# 2led_Arduino_V2.net
KiCad netlist of a schematic drawn in EAGLE
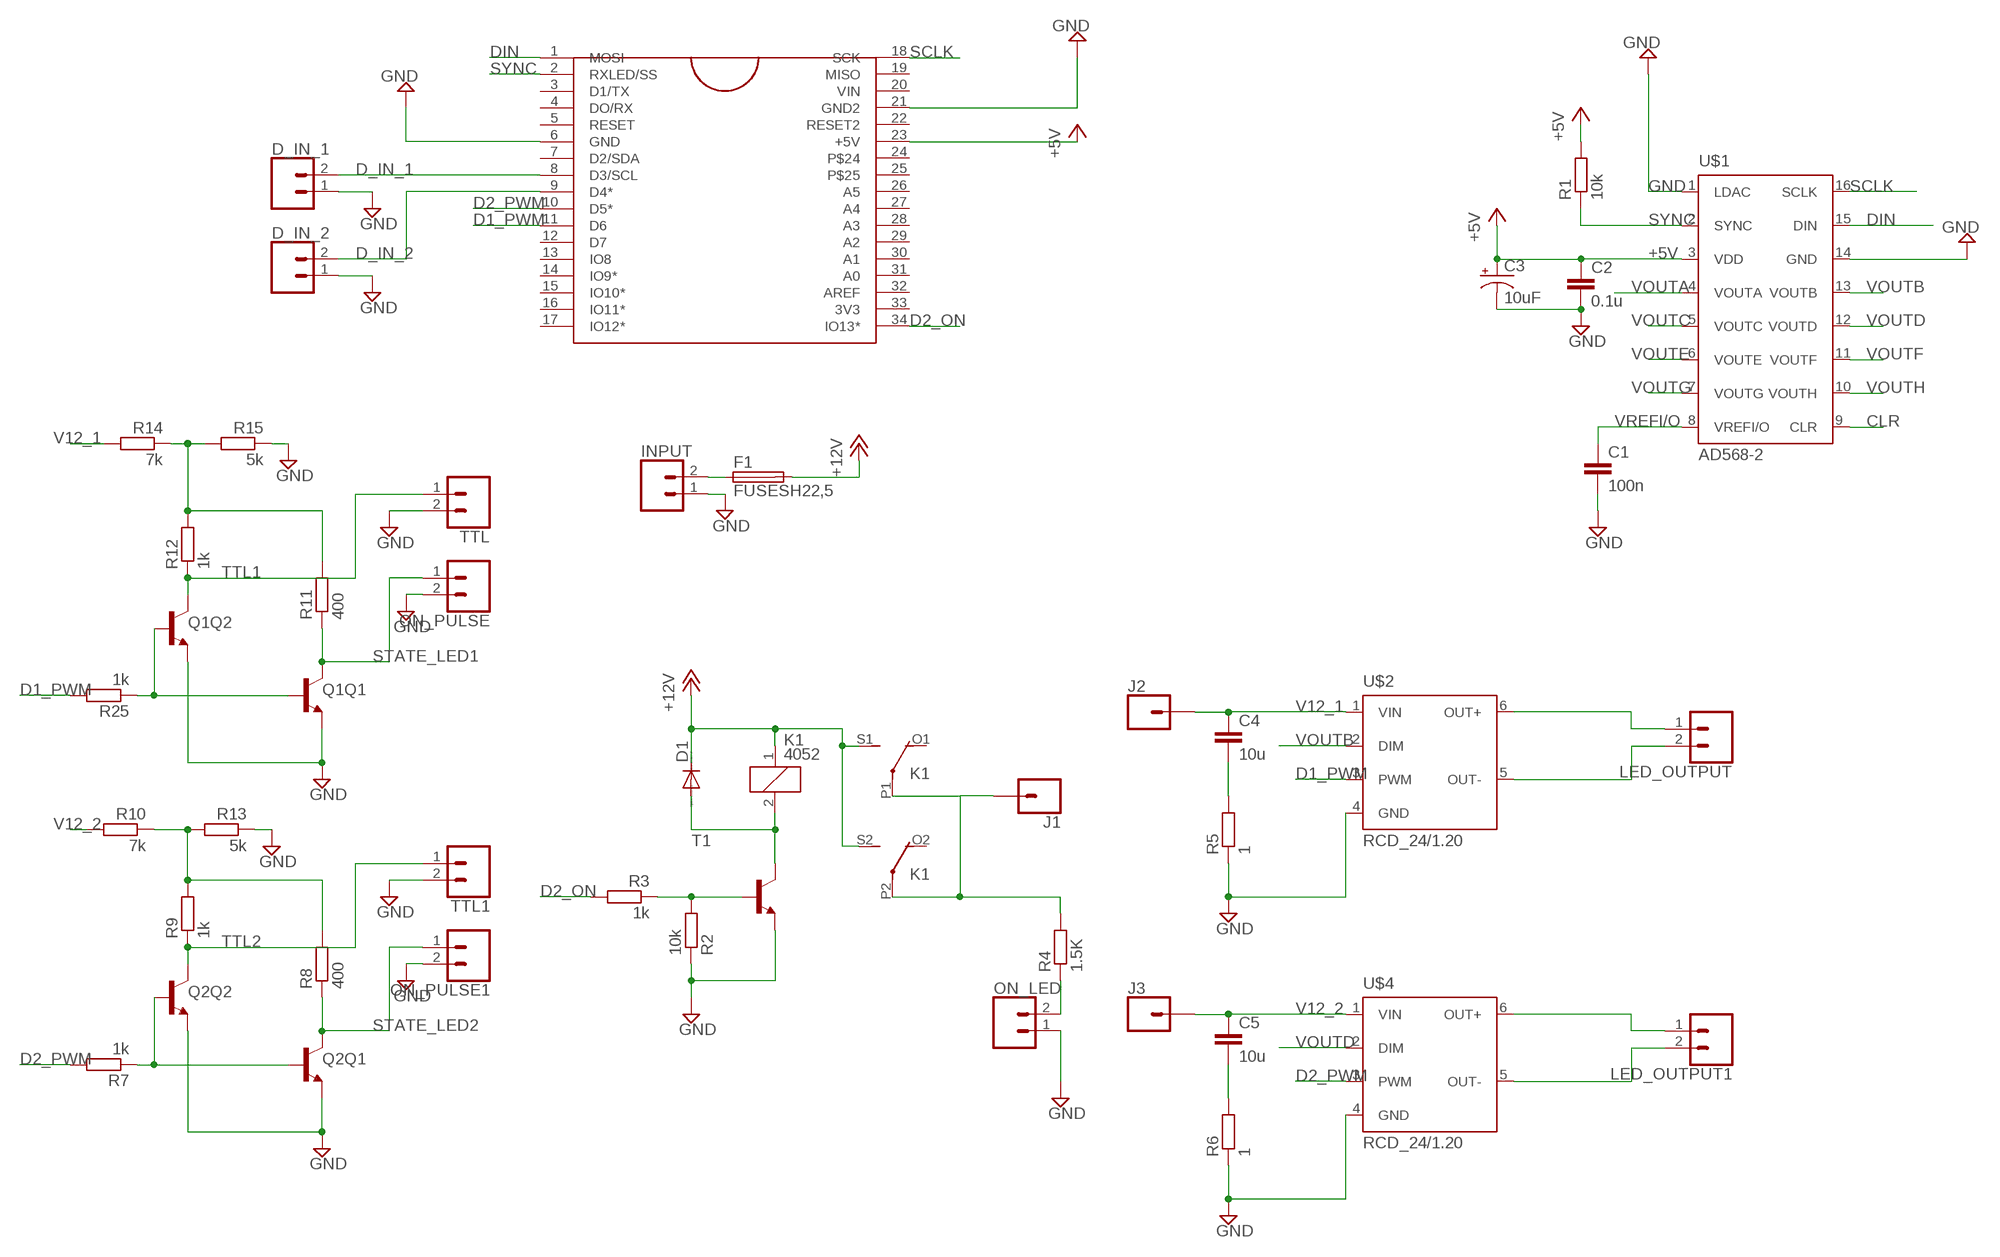
[diagram p0: schematic, sheet 1]

(export (version "E")
  (design (tool "Eeschema 10.0.6"))
  (components
    (comp (ref "C1")
      (value "100n")
      (footprint "eagle-import:C1206")
      (libsource (lib "eagle-import") (part "C-EUC1206"))
    )
    (comp (ref "C2")
      (value "0.1u")
      (footprint "eagle-import:C1206")
      (libsource (lib "eagle-import") (part "C-EUC1206"))
    )
    (comp (ref "C3")
      (value "10uF")
      (footprint "eagle-import:EIA3528")
      (libsource (lib "eagle-import") (part "10UF-POLAR-EIA3528-20V-10%(TANT)"))
    )
    (comp (ref "C4")
      (value "10u")
      (footprint "eagle-import:C1206")
      (libsource (lib "eagle-import") (part "C-EUC1206"))
    )
    (comp (ref "C5")
      (value "10u")
      (footprint "eagle-import:C1206")
      (libsource (lib "eagle-import") (part "C-EUC1206"))
    )
    (comp (ref "D1")
      (value "DIODE-DO214AC")
      (footprint "eagle-import:DO214AC")
      (libsource (lib "eagle-import") (part "DIODE-DO214AC"))
    )
    (comp (ref "D_IN_1")
      (value "CONN_02")
      (footprint "eagle-import:1X02")
      (libsource (lib "eagle-import") (part "CONN_02"))
    )
    (comp (ref "D_IN_2")
      (value "CONN_02")
      (footprint "eagle-import:1X02")
      (libsource (lib "eagle-import") (part "CONN_02"))
    )
    (comp (ref "F1")
      (value "FUSESH22,5")
      (footprint "eagle-import:SH22,5")
      (libsource (lib "eagle-import") (part "FUSESH22,5"))
    )
    (comp (ref "INPUT")
      (value "CONN_023.5MM")
      (footprint "eagle-import:SCREWTERMINAL-3.5MM-2")
      (libsource (lib "eagle-import") (part "CONN_023.5MM"))
    )
    (comp (ref "J1")
      (value "CONN_01")
      (footprint "eagle-import:1X01")
      (libsource (lib "eagle-import") (part "CONN_01"))
    )
    (comp (ref "J2")
      (value "CONN_01")
      (footprint "eagle-import:1X01")
      (libsource (lib "eagle-import") (part "CONN_01"))
    )
    (comp (ref "J3")
      (value "CONN_01")
      (footprint "eagle-import:1X01")
      (libsource (lib "eagle-import") (part "CONN_01"))
    )
    (comp (ref "K1")
      (value "4052")
      (footprint "eagle-import:F4052")
      (libsource (lib "eagle-import") (part "4052"))
    )
    (comp (ref "LED_OUTPUT")
      (value "CONN_023.5MM")
      (footprint "eagle-import:SCREWTERMINAL-3.5MM-2")
      (libsource (lib "eagle-import") (part "CONN_023.5MM"))
    )
    (comp (ref "LED_OUTPUT1")
      (value "CONN_023.5MM")
      (footprint "eagle-import:SCREWTERMINAL-3.5MM-2")
      (libsource (lib "eagle-import") (part "CONN_023.5MM"))
    )
    (comp (ref "ON_LED")
      (value "CONN_02")
      (footprint "eagle-import:1X02")
      (libsource (lib "eagle-import") (part "CONN_02"))
    )
    (comp (ref "ON_PULSE")
      (value "CONN_02")
      (footprint "eagle-import:1X02")
      (libsource (lib "eagle-import") (part "CONN_02"))
    )
    (comp (ref "ON_PULSE1")
      (value "CONN_02")
      (footprint "eagle-import:1X02")
      (libsource (lib "eagle-import") (part "CONN_02"))
    )
    (comp (ref "Q1")
      (value "TRANS_NPN_DUAL_NSM4002-MBT3904DW1T1")
      (footprint "eagle-import:SC70-6")
      (libsource (lib "eagle-import") (part "TRANS_NPN_DUAL_NSM4002-MBT3904DW1T1"))
    )
    (comp (ref "Q2")
      (value "TRANS_NPN_DUAL_NSM4002-MBT3904DW1T1")
      (footprint "eagle-import:SC70-6")
      (libsource (lib "eagle-import") (part "TRANS_NPN_DUAL_NSM4002-MBT3904DW1T1"))
    )
    (comp (ref "R1")
      (value "10k")
      (footprint "eagle-import:R0805")
      (libsource (lib "eagle-import") (part "R-EU_R0805"))
    )
    (comp (ref "R2")
      (value "10k")
      (footprint "eagle-import:R0805")
      (libsource (lib "eagle-import") (part "R-EU_R0805"))
    )
    (comp (ref "R3")
      (value "1k")
      (footprint "eagle-import:R0805")
      (libsource (lib "eagle-import") (part "R-EU_R0805"))
    )
    (comp (ref "R4")
      (value "1.5K")
      (footprint "eagle-import:R0805")
      (libsource (lib "eagle-import") (part "R-EU_R0805"))
    )
    (comp (ref "R5")
      (value "1")
      (footprint "eagle-import:R1206")
      (libsource (lib "eagle-import") (part "R-EU_R1206"))
    )
    (comp (ref "R6")
      (value "1")
      (footprint "eagle-import:R1206")
      (libsource (lib "eagle-import") (part "R-EU_R1206"))
    )
    (comp (ref "R7")
      (value "1k")
      (footprint "eagle-import:R0805")
      (libsource (lib "eagle-import") (part "R-EU_R0805"))
    )
    (comp (ref "R8")
      (value "400")
      (footprint "eagle-import:R0805")
      (libsource (lib "eagle-import") (part "R-EU_R0805"))
    )
    (comp (ref "R9")
      (value "1k")
      (footprint "eagle-import:R0805")
      (libsource (lib "eagle-import") (part "R-EU_R0805"))
    )
    (comp (ref "R10")
      (value "7k")
      (footprint "eagle-import:R0805")
      (libsource (lib "eagle-import") (part "R-EU_R0805"))
    )
    (comp (ref "R11")
      (value "400")
      (footprint "eagle-import:R0805")
      (libsource (lib "eagle-import") (part "R-EU_R0805"))
    )
    (comp (ref "R12")
      (value "1k")
      (footprint "eagle-import:R0805")
      (libsource (lib "eagle-import") (part "R-EU_R0805"))
    )
    (comp (ref "R13")
      (value "5k")
      (footprint "eagle-import:R0805")
      (libsource (lib "eagle-import") (part "R-EU_R0805"))
    )
    (comp (ref "R14")
      (value "7k")
      (footprint "eagle-import:R0805")
      (libsource (lib "eagle-import") (part "R-EU_R0805"))
    )
    (comp (ref "R15")
      (value "5k")
      (footprint "eagle-import:R0805")
      (libsource (lib "eagle-import") (part "R-EU_R0805"))
    )
    (comp (ref "R25")
      (value "1k")
      (footprint "eagle-import:R0805")
      (libsource (lib "eagle-import") (part "R-EU_R0805"))
    )
    (comp (ref "T1")
      (value "-NPN-SOT223")
      (footprint "eagle-import:SOT223")
      (libsource (lib "eagle-import") (part "-NPN-SOT223"))
    )
    (comp (ref "TTL")
      (value "CONN_02")
      (footprint "eagle-import:1X02")
      (libsource (lib "eagle-import") (part "CONN_02"))
    )
    (comp (ref "TTL1")
      (value "CONN_02")
      (footprint "eagle-import:1X02")
      (libsource (lib "eagle-import") (part "CONN_02"))
    )
    (comp (ref "U$1")
      (value "AD568-2")
      (footprint "eagle-import:TSSOP-16")
      (libsource (lib "eagle-import") (part "AD568-2"))
    )
    (comp (ref "U$2")
      (value "RCD_24/1.20")
      (footprint "eagle-import:RCD-24_W_X3")
      (libsource (lib "eagle-import") (part "RCD_24/1.20"))
    )
    (comp (ref "U$3")
      (value "ARDUINO_MICRO")
      (footprint "eagle-import:ARDUINO_MICRO_PADS")
      (fields (field (name "SPICEPREFIX") "X"))
      (libsource (lib "eagle-import") (part "ARDUINO_MICRO"))
    )
    (comp (ref "U$4")
      (value "RCD_24/1.20")
      (footprint "eagle-import:RCD-24_W_X3")
      (libsource (lib "eagle-import") (part "RCD_24/1.20"))
    )
  )
  (nets
    (net (code "1") (name "+5V") (class "Default")
      (node (ref "C2") (pin "1") (pinfunction "1_1") (pintype "passive"))
      (node (ref "C3") (pin "A") (pinfunction "+_A") (pintype "passive"))
      (node (ref "R1") (pin "2") (pinfunction "2_2") (pintype "passive"))
      (node (ref "U$1") (pin "3") (pinfunction "VDD_3") (pintype "power_in"))
      (node (ref "U$3") (pin "23") (pinfunction "+5V_23") (pintype "bidirectional"))
    )
    (net (code "2") (name "+12V") (class "Default")
      (node (ref "D1") (pin "C") (pinfunction "C_C") (pintype "passive"))
      (node (ref "F1") (pin "2") (pinfunction "2_2") (pintype "passive"))
      (node (ref "K1") (pin "1") (pinfunction "1_1") (pintype "passive"))
      (node (ref "K1") (pin "S1") (pinfunction "S_S1") (pintype "passive"))
      (node (ref "K1") (pin "S2") (pinfunction "S_S2") (pintype "passive"))
    )
    (net (code "3") (name "/CLR") (class "Default")
      (node (ref "U$1") (pin "9") (pinfunction "CLR_9") (pintype "output"))
    )
    (net (code "4") (name "/D1_PWM") (class "Default")
      (node (ref "R25") (pin "2") (pinfunction "2_2") (pintype "passive"))
      (node (ref "U$2") (pin "3") (pinfunction "PWM_3") (pintype "passive"))
      (node (ref "U$3") (pin "11") (pinfunction "D6_11") (pintype "bidirectional"))
    )
    (net (code "5") (name "/D2_ON") (class "Default")
      (node (ref "R3") (pin "2") (pinfunction "2_2") (pintype "passive"))
      (node (ref "U$3") (pin "34") (pinfunction "IO13*_34") (pintype "bidirectional"))
    )
    (net (code "6") (name "/D2_PWM") (class "Default")
      (node (ref "R7") (pin "2") (pinfunction "2_2") (pintype "passive"))
      (node (ref "U$3") (pin "10") (pinfunction "D5*_10") (pintype "bidirectional"))
      (node (ref "U$4") (pin "3") (pinfunction "PWM_3") (pintype "passive"))
    )
    (net (code "7") (name "/DIN") (class "Default")
      (node (ref "U$1") (pin "15") (pinfunction "DIN_15") (pintype "input"))
      (node (ref "U$3") (pin "1") (pinfunction "MOSI_1") (pintype "bidirectional"))
    )
    (net (code "8") (name "/D_IN_1") (class "Default")
      (node (ref "D_IN_1") (pin "2") (pinfunction "2_2") (pintype "passive"))
      (node (ref "U$3") (pin "8") (pinfunction "D3/SCL_8") (pintype "bidirectional"))
    )
    (net (code "9") (name "/D_IN_2") (class "Default")
      (node (ref "D_IN_2") (pin "2") (pinfunction "2_2") (pintype "passive"))
      (node (ref "U$3") (pin "9") (pinfunction "D4*_9") (pintype "bidirectional"))
    )
    (net (code "10") (name "/SCLK") (class "Default")
      (node (ref "U$1") (pin "16") (pinfunction "SCLK_16") (pintype "input"))
      (node (ref "U$3") (pin "18") (pinfunction "SCK_18") (pintype "bidirectional"))
    )
    (net (code "11") (name "/STATE_LED1") (class "Default")
      (node (ref "ON_PULSE") (pin "1") (pinfunction "1_1") (pintype "passive"))
      (node (ref "Q1") (pin "3") (pinfunction "C_3") (pintype "passive"))
      (node (ref "R11") (pin "1") (pinfunction "1_1") (pintype "passive"))
    )
    (net (code "12") (name "/STATE_LED2") (class "Default")
      (node (ref "ON_PULSE1") (pin "1") (pinfunction "1_1") (pintype "passive"))
      (node (ref "Q2") (pin "3") (pinfunction "C_3") (pintype "passive"))
      (node (ref "R8") (pin "1") (pinfunction "1_1") (pintype "passive"))
    )
    (net (code "13") (name "/SYNC") (class "Default")
      (node (ref "R1") (pin "1") (pinfunction "1_1") (pintype "passive"))
      (node (ref "U$1") (pin "2") (pinfunction "SYNC_2") (pintype "input"))
      (node (ref "U$3") (pin "2") (pinfunction "RXLED/SS_2") (pintype "bidirectional"))
    )
    (net (code "14") (name "/TTL1") (class "Default")
      (node (ref "Q1") (pin "6") (pinfunction "C_6") (pintype "passive"))
      (node (ref "R12") (pin "1") (pinfunction "1_1") (pintype "passive"))
      (node (ref "TTL") (pin "1") (pinfunction "1_1") (pintype "passive"))
    )
    (net (code "15") (name "/TTL2") (class "Default")
      (node (ref "Q2") (pin "6") (pinfunction "C_6") (pintype "passive"))
      (node (ref "R9") (pin "1") (pinfunction "1_1") (pintype "passive"))
      (node (ref "TTL1") (pin "1") (pinfunction "1_1") (pintype "passive"))
    )
    (net (code "16") (name "/V12_1") (class "Default")
      (node (ref "C4") (pin "1") (pinfunction "1_1") (pintype "passive"))
      (node (ref "J2") (pin "1") (pinfunction "1_1") (pintype "passive"))
      (node (ref "R14") (pin "2") (pinfunction "2_2") (pintype "passive"))
      (node (ref "U$2") (pin "1") (pinfunction "VIN_1") (pintype "input"))
    )
    (net (code "17") (name "/V12_2") (class "Default")
      (node (ref "C5") (pin "1") (pinfunction "1_1") (pintype "passive"))
      (node (ref "J3") (pin "1") (pinfunction "1_1") (pintype "passive"))
      (node (ref "R10") (pin "2") (pinfunction "2_2") (pintype "passive"))
      (node (ref "U$4") (pin "1") (pinfunction "VIN_1") (pintype "input"))
    )
    (net (code "18") (name "/VOUTA") (class "Default")
      (node (ref "U$1") (pin "4") (pinfunction "VOUTA_4") (pintype "output"))
    )
    (net (code "19") (name "/VOUTB") (class "Default")
      (node (ref "U$1") (pin "13") (pinfunction "VOUTB_13") (pintype "output"))
      (node (ref "U$2") (pin "2") (pinfunction "DIM_2") (pintype "passive"))
    )
    (net (code "20") (name "/VOUTC") (class "Default")
      (node (ref "U$1") (pin "5") (pinfunction "VOUTC_5") (pintype "output"))
    )
    (net (code "21") (name "/VOUTD") (class "Default")
      (node (ref "U$1") (pin "12") (pinfunction "VOUTD_12") (pintype "output"))
      (node (ref "U$4") (pin "2") (pinfunction "DIM_2") (pintype "passive"))
    )
    (net (code "22") (name "/VOUTE") (class "Default")
      (node (ref "U$1") (pin "6") (pinfunction "VOUTE_6") (pintype "output"))
    )
    (net (code "23") (name "/VOUTF") (class "Default")
      (node (ref "U$1") (pin "11") (pinfunction "VOUTF_11") (pintype "output"))
    )
    (net (code "24") (name "/VOUTG") (class "Default")
      (node (ref "U$1") (pin "7") (pinfunction "VOUTG_7") (pintype "output"))
    )
    (net (code "25") (name "/VOUTH") (class "Default")
      (node (ref "U$1") (pin "10") (pinfunction "VOUTH_10") (pintype "output"))
    )
    (net (code "26") (name "/VREFI{slash}O") (class "Default")
      (node (ref "C1") (pin "1") (pinfunction "1_1") (pintype "passive"))
      (node (ref "U$1") (pin "8") (pinfunction "VREFI/O_8") (pintype "output"))
    )
    (net (code "27") (name "GND") (class "Default")
      (node (ref "C1") (pin "2") (pinfunction "2_2") (pintype "passive"))
      (node (ref "C2") (pin "2") (pinfunction "2_2") (pintype "passive"))
      (node (ref "C3") (pin "C") (pinfunction "-_C") (pintype "passive"))
      (node (ref "D_IN_1") (pin "1") (pinfunction "1_1") (pintype "passive"))
      (node (ref "D_IN_2") (pin "1") (pinfunction "1_1") (pintype "passive"))
      (node (ref "INPUT") (pin "1") (pinfunction "1_1") (pintype "passive"))
      (node (ref "ON_LED") (pin "1") (pinfunction "1_1") (pintype "passive"))
      (node (ref "ON_PULSE") (pin "2") (pinfunction "2_2") (pintype "passive"))
      (node (ref "ON_PULSE1") (pin "2") (pinfunction "2_2") (pintype "passive"))
      (node (ref "Q1") (pin "1") (pinfunction "E_1") (pintype "passive"))
      (node (ref "Q1") (pin "4") (pinfunction "E_4") (pintype "passive"))
      (node (ref "Q2") (pin "1") (pinfunction "E_1") (pintype "passive"))
      (node (ref "Q2") (pin "4") (pinfunction "E_4") (pintype "passive"))
      (node (ref "R13") (pin "1") (pinfunction "1_1") (pintype "passive"))
      (node (ref "R15") (pin "1") (pinfunction "1_1") (pintype "passive"))
      (node (ref "R2") (pin "1") (pinfunction "1_1") (pintype "passive"))
      (node (ref "R5") (pin "1") (pinfunction "1_1") (pintype "passive"))
      (node (ref "R6") (pin "1") (pinfunction "1_1") (pintype "passive"))
      (node (ref "T1") (pin "3") (pinfunction "E_3") (pintype "passive"))
      (node (ref "TTL") (pin "2") (pinfunction "2_2") (pintype "passive"))
      (node (ref "TTL1") (pin "2") (pinfunction "2_2") (pintype "passive"))
      (node (ref "U$1") (pin "1") (pinfunction "LDAC_1") (pintype "bidirectional"))
      (node (ref "U$1") (pin "14") (pinfunction "GND_14") (pintype "power_in"))
      (node (ref "U$2") (pin "4") (pinfunction "GND_4") (pintype "power_in"))
      (node (ref "U$3") (pin "21") (pinfunction "GND2_21") (pintype "power_in"))
      (node (ref "U$3") (pin "6") (pinfunction "GND_6") (pintype "power_in"))
      (node (ref "U$4") (pin "4") (pinfunction "GND_4") (pintype "power_in"))
    )
    (net (code "28") (name "Net-(C4-Pad2)") (class "Default")
      (node (ref "C4") (pin "2") (pinfunction "2_2") (pintype "passive"))
      (node (ref "R5") (pin "2") (pinfunction "2_2") (pintype "passive"))
    )
    (net (code "29") (name "Net-(C5-Pad2)") (class "Default")
      (node (ref "C5") (pin "2") (pinfunction "2_2") (pintype "passive"))
      (node (ref "R6") (pin "2") (pinfunction "2_2") (pintype "passive"))
    )
    (net (code "30") (name "Net-(F1-Pad1)") (class "Default")
      (node (ref "F1") (pin "1") (pinfunction "1_1") (pintype "passive"))
      (node (ref "INPUT") (pin "2") (pinfunction "2_2") (pintype "passive"))
    )
    (net (code "31") (name "Net-(K1B-P)") (class "Default")
      (node (ref "J1") (pin "1") (pinfunction "1_1") (pintype "passive"))
      (node (ref "K1") (pin "P1") (pinfunction "P_P1") (pintype "passive"))
      (node (ref "K1") (pin "P2") (pinfunction "P_P2") (pintype "passive"))
      (node (ref "R4") (pin "2") (pinfunction "2_2") (pintype "passive"))
    )
    (net (code "32") (name "Net-(ON_LED-Pad2)") (class "Default")
      (node (ref "ON_LED") (pin "2") (pinfunction "2_2") (pintype "passive"))
      (node (ref "R4") (pin "1") (pinfunction "1_1") (pintype "passive"))
    )
    (net (code "33") (name "Net-(Q1A-B)") (class "Default")
      (node (ref "Q1") (pin "2") (pinfunction "B_2") (pintype "passive"))
      (node (ref "Q1") (pin "5") (pinfunction "B_5") (pintype "passive"))
      (node (ref "R25") (pin "1") (pinfunction "1_1") (pintype "passive"))
    )
    (net (code "34") (name "Net-(Q2A-B)") (class "Default")
      (node (ref "Q2") (pin "2") (pinfunction "B_2") (pintype "passive"))
      (node (ref "Q2") (pin "5") (pinfunction "B_5") (pintype "passive"))
      (node (ref "R7") (pin "1") (pinfunction "1_1") (pintype "passive"))
    )
    (net (code "35") (name "Net-(R10-Pad1)") (class "Default")
      (node (ref "R10") (pin "1") (pinfunction "1_1") (pintype "passive"))
      (node (ref "R13") (pin "2") (pinfunction "2_2") (pintype "passive"))
      (node (ref "R8") (pin "2") (pinfunction "2_2") (pintype "passive"))
      (node (ref "R9") (pin "2") (pinfunction "2_2") (pintype "passive"))
    )
    (net (code "36") (name "Net-(R11-Pad2)") (class "Default")
      (node (ref "R11") (pin "2") (pinfunction "2_2") (pintype "passive"))
      (node (ref "R12") (pin "2") (pinfunction "2_2") (pintype "passive"))
      (node (ref "R14") (pin "1") (pinfunction "1_1") (pintype "passive"))
      (node (ref "R15") (pin "2") (pinfunction "2_2") (pintype "passive"))
    )
    (net (code "37") (name "Net-(T1-B)") (class "Default")
      (node (ref "R2") (pin "2") (pinfunction "2_2") (pintype "passive"))
      (node (ref "R3") (pin "1") (pinfunction "1_1") (pintype "passive"))
      (node (ref "T1") (pin "1") (pinfunction "B_1") (pintype "passive"))
    )
    (net (code "38") (name "Net-(T1-C)") (class "Default")
      (node (ref "D1") (pin "A") (pinfunction "A_A") (pintype "passive"))
      (node (ref "K1") (pin "2") (pinfunction "2_2") (pintype "passive"))
      (node (ref "T1") (pin "4") (pinfunction "C_4") (pintype "passive"))
    )
    (net (code "39") (name "Net-(U$2-OUT+)") (class "Default")
      (node (ref "LED_OUTPUT") (pin "1") (pinfunction "1_1") (pintype "passive"))
      (node (ref "U$2") (pin "6") (pinfunction "OUT+_6") (pintype "output"))
    )
    (net (code "40") (name "Net-(U$2-OUT-)") (class "Default")
      (node (ref "LED_OUTPUT") (pin "2") (pinfunction "2_2") (pintype "passive"))
      (node (ref "U$2") (pin "5") (pinfunction "OUT-_5") (pintype "output"))
    )
    (net (code "41") (name "Net-(U$4-OUT+)") (class "Default")
      (node (ref "LED_OUTPUT1") (pin "1") (pinfunction "1_1") (pintype "passive"))
      (node (ref "U$4") (pin "6") (pinfunction "OUT+_6") (pintype "output"))
    )
    (net (code "42") (name "Net-(U$4-OUT-)") (class "Default")
      (node (ref "LED_OUTPUT1") (pin "2") (pinfunction "2_2") (pintype "passive"))
      (node (ref "U$4") (pin "5") (pinfunction "OUT-_5") (pintype "output"))
    )
    (net (code "43") (name "unconnected-(K1B-O-PadO1)") (class "Default")
      (node (ref "K1") (pin "O1") (pinfunction "O_O1") (pintype "passive"))
    )
    (net (code "44") (name "unconnected-(K1C-O-PadO2)") (class "Default")
      (node (ref "K1") (pin "O2") (pinfunction "O_O2") (pintype "passive"))
    )
    (net (code "45") (name "unconnected-(U$3-3V3-Pad33)") (class "Default")
      (node (ref "U$3") (pin "33") (pinfunction "3V3_33") (pintype "bidirectional"))
    )
    (net (code "46") (name "unconnected-(U$3-A0-Pad31)") (class "Default")
      (node (ref "U$3") (pin "31") (pinfunction "A0_31") (pintype "bidirectional"))
    )
    (net (code "47") (name "unconnected-(U$3-A1-Pad30)") (class "Default")
      (node (ref "U$3") (pin "30") (pinfunction "A1_30") (pintype "bidirectional"))
    )
    (net (code "48") (name "unconnected-(U$3-A2-Pad29)") (class "Default")
      (node (ref "U$3") (pin "29") (pinfunction "A2_29") (pintype "bidirectional"))
    )
    (net (code "49") (name "unconnected-(U$3-A3-Pad28)") (class "Default")
      (node (ref "U$3") (pin "28") (pinfunction "A3_28") (pintype "bidirectional"))
    )
    (net (code "50") (name "unconnected-(U$3-A4-Pad27)") (class "Default")
      (node (ref "U$3") (pin "27") (pinfunction "A4_27") (pintype "bidirectional"))
    )
    (net (code "51") (name "unconnected-(U$3-A5-Pad26)") (class "Default")
      (node (ref "U$3") (pin "26") (pinfunction "A5_26") (pintype "bidirectional"))
    )
    (net (code "52") (name "unconnected-(U$3-AREF-Pad32)") (class "Default")
      (node (ref "U$3") (pin "32") (pinfunction "AREF_32") (pintype "bidirectional"))
    )
    (net (code "53") (name "unconnected-(U$3-D1{slash}TX-Pad3)") (class "Default")
      (node (ref "U$3") (pin "3") (pinfunction "D1/TX_3") (pintype "bidirectional"))
    )
    (net (code "54") (name "unconnected-(U$3-D2{slash}SDA-Pad7)") (class "Default")
      (node (ref "U$3") (pin "7") (pinfunction "D2/SDA_7") (pintype "bidirectional"))
    )
    (net (code "55") (name "unconnected-(U$3-D7-Pad12)") (class "Default")
      (node (ref "U$3") (pin "12") (pinfunction "D7_12") (pintype "bidirectional"))
    )
    (net (code "56") (name "unconnected-(U$3-DO{slash}RX-Pad4)") (class "Default")
      (node (ref "U$3") (pin "4") (pinfunction "DO/RX_4") (pintype "bidirectional"))
    )
    (net (code "57") (name "unconnected-(U$3-IO8-Pad13)") (class "Default")
      (node (ref "U$3") (pin "13") (pinfunction "IO8_13") (pintype "bidirectional"))
    )
    (net (code "58") (name "unconnected-(U$3-IO9*-Pad14)") (class "Default")
      (node (ref "U$3") (pin "14") (pinfunction "IO9*_14") (pintype "bidirectional"))
    )
    (net (code "59") (name "unconnected-(U$3-IO10*-Pad15)") (class "Default")
      (node (ref "U$3") (pin "15") (pinfunction "IO10*_15") (pintype "bidirectional"))
    )
    (net (code "60") (name "unconnected-(U$3-IO11*-Pad16)") (class "Default")
      (node (ref "U$3") (pin "16") (pinfunction "IO11*_16") (pintype "bidirectional"))
    )
    (net (code "61") (name "unconnected-(U$3-IO12*-Pad17)") (class "Default")
      (node (ref "U$3") (pin "17") (pinfunction "IO12*_17") (pintype "bidirectional"))
    )
    (net (code "62") (name "unconnected-(U$3-MISO-Pad19)") (class "Default")
      (node (ref "U$3") (pin "19") (pinfunction "MISO_19") (pintype "bidirectional"))
    )
    (net (code "63") (name "unconnected-(U$3-P$24-Pad24)") (class "Default")
      (node (ref "U$3") (pin "24") (pinfunction "P$24_24") (pintype "bidirectional"))
    )
    (net (code "64") (name "unconnected-(U$3-P$25-Pad25)") (class "Default")
      (node (ref "U$3") (pin "25") (pinfunction "P$25_25") (pintype "bidirectional"))
    )
    (net (code "65") (name "unconnected-(U$3-RESET-Pad5)") (class "Default")
      (node (ref "U$3") (pin "5") (pinfunction "RESET_5") (pintype "bidirectional"))
    )
    (net (code "66") (name "unconnected-(U$3-RESET2-Pad22)") (class "Default")
      (node (ref "U$3") (pin "22") (pinfunction "RESET2_22") (pintype "bidirectional"))
    )
    (net (code "67") (name "unconnected-(U$3-VIN-Pad20)") (class "Default")
      (node (ref "U$3") (pin "20") (pinfunction "VIN_20") (pintype "bidirectional"))
    )
  )
)
